# Input_Stage.net
KiCad netlist of a schematic drawn in Altium Designer
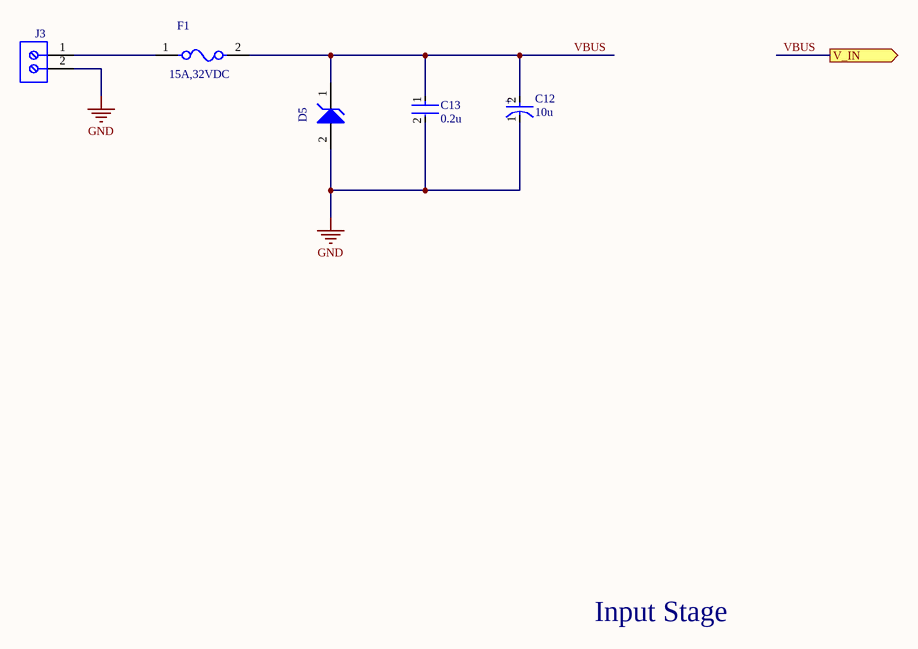
[diagram p0: Input_Stage.SchDoc]

(export (version "E")
  (design (tool "Eeschema 10.0.6"))
  (components
    (comp (ref "C12")
      (value "10u")
      (footprint "FP-RAD-TH-D_10_0_5-L_16_1-MFG")
      (description "Aluminum Electrolytic Capacitors (Radial Lead Type) AEC-Q200 Qualified 820uF ±20% 10V")
      (fields (field (name "VOLTAGE") "10V") (field (name "TOLERANCE") "20%"))
      (libsource (lib "Altium Content Vault") (part "a00bbbee19879c290e62620ae7e47b1"))
    )
    (comp (ref "C13")
      (value "0.2u")
      (footprint "FP-C0805C-DN-MFG")
      (description "CAP CER 0.1UF 50V X7R 0805")
      (fields
        (field (name "MANUFACTURER PART NUMBER") "C0805C104K5RACTU")
        (field (name "MANUFACTURER") "KEMET")
      )
      (libsource (lib "Altium Content Vault") (part "b4654b650e69147ec39a6b967a45e02"))
    )
    (comp (ref "D5")
      (value "824540301")
      (footprint "WE-TVSP_DO-214AB_Unidirectional")
      (description "Tvs Diode, 1.5KW, 30V, Unidir, DO-214AB")
      (libsource (lib "Altium Content Vault") (part "WE-TVSP_Unidirectional"))
    )
    (comp (ref "F1")
      (value "15A,32VDC")
      (footprint "FP-SF-1206HHA-R-MFG")
      (description "SF-1206HHA1500R-2 Fuse Chip 15A 50V SMD Solder Pad 1206 3.2 X 1.65 X 1mm")
      (libsource (lib "Altium Content Vault") (part "5bcf9b9f640e542cf0359d10258e979"))
    )
    (comp (ref "J3")
      (value "691134710002")
      (footprint "691134710002")
      (description "Wire-To-Board Terminal Block, 5mm Pitch, Horizontal, Screw, 2 Poles")
      (libsource (lib "Altium Content Vault") (part "TBL - 1R - 02P - Screw"))
    )
  )
  (nets
    (net (code "1") (name "/VBUS") (class "Default")
      (node (ref "C12") (pin "2") (pinfunction "A_2") (pintype "passive"))
      (node (ref "C13") (pin "1") (pinfunction "1_1") (pintype "passive"))
      (node (ref "D5") (pin "1") (pinfunction "K_1") (pintype "passive"))
      (node (ref "F1") (pin "2") (pinfunction "2_2") (pintype "passive"))
    )
    (net (code "2") (name "GND") (class "Default")
      (node (ref "C12") (pin "1") (pinfunction "C_1") (pintype "passive"))
      (node (ref "C13") (pin "2") (pinfunction "2_2") (pintype "passive"))
      (node (ref "D5") (pin "2") (pinfunction "A_2") (pintype "passive"))
      (node (ref "J3") (pin "2") (pinfunction "2_2") (pintype "passive"))
    )
    (net (code "3") (name "Net-(F1-Pad1)") (class "Default")
      (node (ref "F1") (pin "1") (pinfunction "1_1") (pintype "passive"))
      (node (ref "J3") (pin "1") (pinfunction "1_1") (pintype "passive"))
    )
  )
)
